# esp32.net
KiCad netlist of a schematic drawn in Altium Designer
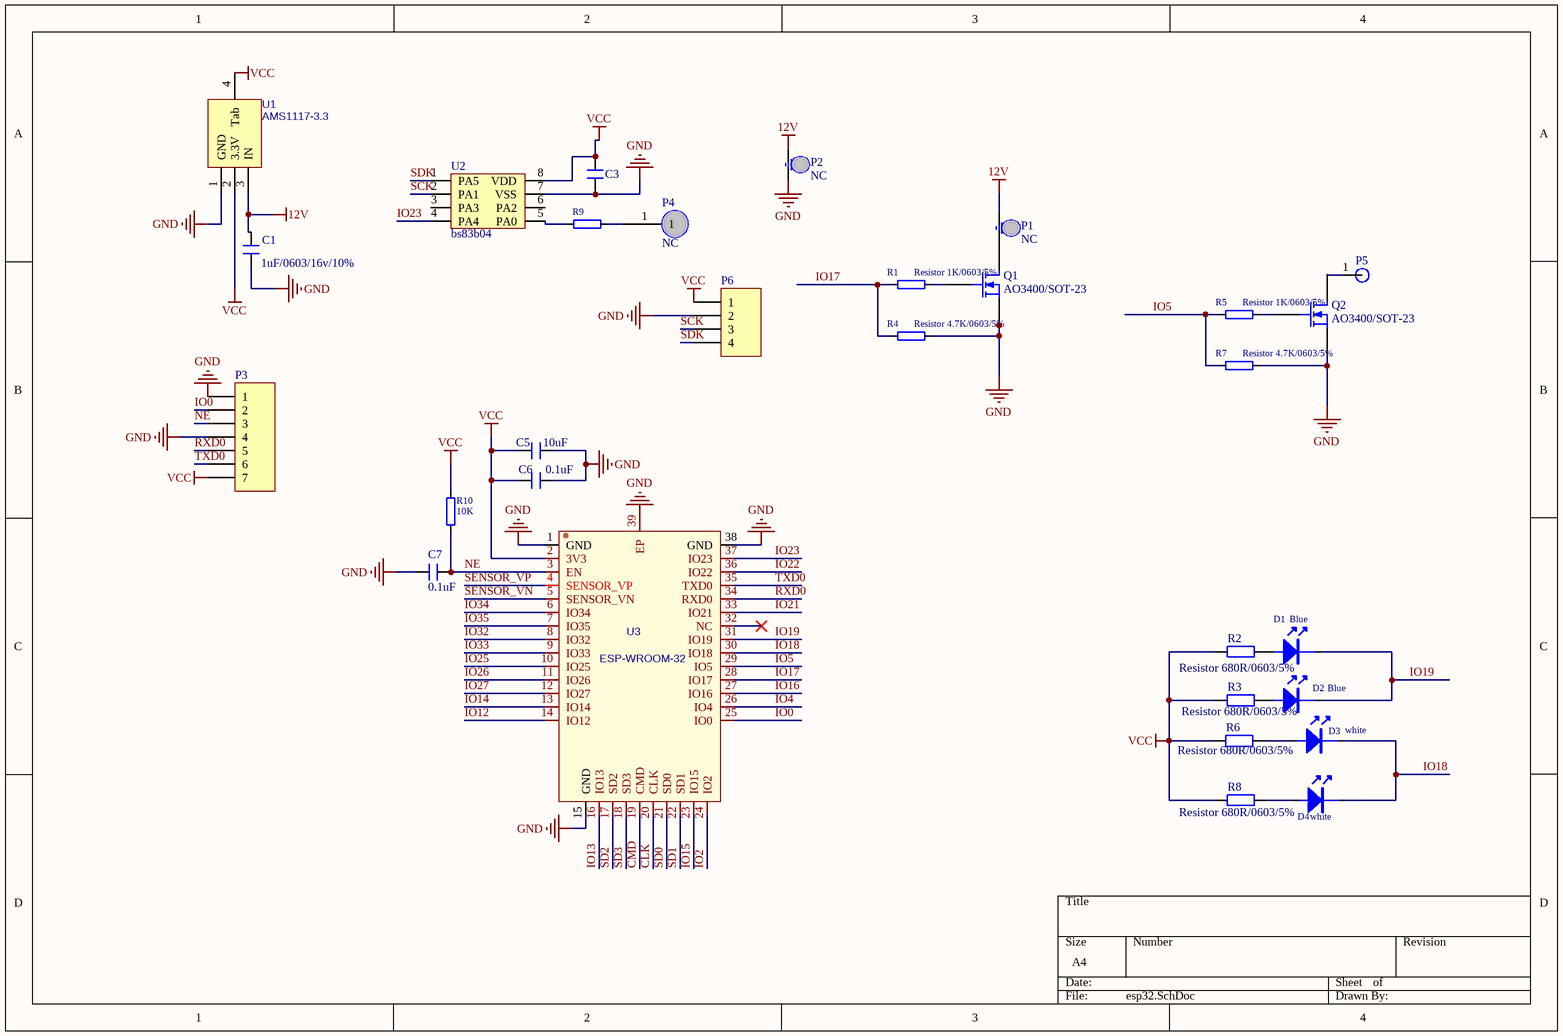
[diagram p0: esp32.SchDoc]

(export (version "E")
  (design (tool "Eeschema 10.0.6"))
  (components
    (comp (ref "C1")
      (value "1uF/0603/16v/10%")
      (footprint "C0603")
      (libsource (lib "Ht_onekey") (part "C0603"))
    )
    (comp (ref "C3")
      (value "100nF")
      (footprint "C0603")
      (description "100nF/0603/16v/10%")
      (libsource (lib "Ht_onekey") (part "C0603"))
    )
    (comp (ref "C5") (value "10uF") (footprint "C0603") (libsource (lib "esp32") (part "C0603")))
    (comp (ref "C6") (value "0.1uF") (footprint "C0603") (libsource (lib "esp32") (part "C0603")))
    (comp (ref "C7") (value "0.1uF") (footprint "C0603") (libsource (lib "esp32") (part "C0603")))
    (comp (ref "D1") (value "Blue") (footprint "1206反贴LED") (libsource (lib "aiwise") (part "LED")))
    (comp (ref "D2") (value "Blue") (footprint "1206反贴LED") (libsource (lib "aiwise") (part "LED")))
    (comp (ref "D3") (value "white") (footprint "1206反贴LED") (libsource (lib "aiwise") (part "LED")))
    (comp (ref "D4") (value "white") (footprint "1206反贴LED") (libsource (lib "aiwise") (part "LED")))
    (comp (ref "P1") (value "NC") (footprint "PAD_2") (libsource (lib "Ht_onekey") (part "Light")))
    (comp (ref "P2") (value "NC") (footprint "PAD_2") (libsource (lib "Ht_onekey") (part "Light")))
    (comp (ref "P3")
      (value "Header 7")
      (footprint "HDR1X7")
      (description "Header, 7-Pin")
      (fields (field (name "PUBLISHER") "Altium Limited"))
      (libsource (lib "Miscellaneous Connectors") (part "Header 7"))
    )
    (comp (ref "P4") (value "NC") (footprint "TOUCH_PAD") (libsource (lib "Ht_onekey") (part "TOUCH_PAD")))
    (comp (ref "P5") (value "PAD") (footprint "PAD") (libsource (lib "esp32") (part "PAD")))
    (comp (ref "P6")
      (value "Header 4")
      (footprint "HDR1X4")
      (description "Header, 4-Pin")
      (fields (field (name "PUBLISHER") "Altium Limited"))
      (libsource (lib "Miscellaneous Connectors") (part "Header 4"))
    )
    (comp (ref "Q1")
      (value "AO3400/SOT-23")
      (footprint "SOT_23_N-MOS")
      (fields (field (name "PUBLISHER") "Altium Limited"))
      (libsource (lib "Miscellaneous Devices") (part "MOSFET-N"))
    )
    (comp (ref "Q2")
      (value "AO3400/SOT-23")
      (footprint "SOT_23_N-MOS")
      (fields (field (name "PUBLISHER") "Altium Limited"))
      (libsource (lib "Miscellaneous Devices") (part "MOSFET-N"))
    )
    (comp (ref "R1") (value "Resistor 1K/0603/5%") (footprint "R0603") (libsource (lib "*") (part "RES")))
    (comp (ref "R2")
      (value "Resistor 680R/0603/5%")
      (footprint "R0603")
      (description "Resistor 2.2K/0603/5%")
      (fields (field (name "PUBLISHER") "Altium Limited"))
      (libsource (lib "Miscellaneous Devices") (part "Res2"))
    )
    (comp (ref "R3")
      (value "Resistor 680R/0603/5%")
      (footprint "R0603")
      (description "Resistor 2.2K/0603/5%")
      (fields (field (name "PUBLISHER") "Altium Limited"))
      (libsource (lib "Miscellaneous Devices") (part "Res2"))
    )
    (comp (ref "R4") (value "Resistor 4.7K/0603/5%") (footprint "R0603") (libsource (lib "*") (part "RES")))
    (comp (ref "R5") (value "Resistor 1K/0603/5%") (footprint "R0603") (libsource (lib "*") (part "RES")))
    (comp (ref "R6")
      (value "Resistor 680R/0603/5%")
      (footprint "R0603")
      (description "Resistor 2.2K/0603/5%")
      (fields (field (name "PUBLISHER") "Altium Limited"))
      (libsource (lib "Miscellaneous Devices") (part "Res2"))
    )
    (comp (ref "R7") (value "Resistor 4.7K/0603/5%") (footprint "R0603") (libsource (lib "*") (part "RES")))
    (comp (ref "R8")
      (value "Resistor 680R/0603/5%")
      (footprint "R0603")
      (description "Resistor 2.2K/0603/5%")
      (fields (field (name "PUBLISHER") "Altium Limited"))
      (libsource (lib "Miscellaneous Devices") (part "Res2"))
    )
    (comp (ref "R9") (value "Resistor 1K/0603/5%") (footprint "R0603") (libsource (lib "*") (part "RES")))
    (comp (ref "R10") (value "10K") (footprint "R0603") (libsource (lib "esp32") (part "RES")))
    (comp (ref "U1")
      (value "AMS1117-3.3")
      (footprint "SOT-223_L6.5-W3.5-P2.30-LS7.0-BR")
      (fields (field (name "BOM_SUPPLIER PART") "C165482") (field (name "CONTRIBUTOR") "LCSC"))
      (libsource (lib "esp32") (part "AMS1117-3.3"))
    )
    (comp (ref "U2")
      (value "bs83b04")
      (footprint "SOP8 - duplicate - duplicate")
      (libsource (lib "esp32") (part "ASC0130C"))
    )
    (comp (ref "U3")
      (value "ESP-WROOM-32")
      (footprint "ESP-WROOM-32")
      (fields (field (name "BOM_SUPPLIER PART") "C95209"))
      (libsource (lib "esp32") (part "ESP-WROOM-32"))
    )
  )
  (nets
    (net (code "1") (name "/CLK") (class "Default")
      (node (ref "U3") (pin "20") (pinfunction "CLK_20") (pintype "passive"))
    )
    (net (code "2") (name "/CMD") (class "Default")
      (node (ref "U3") (pin "19") (pinfunction "CMD_19") (pintype "passive"))
    )
    (net (code "3") (name "/IO0") (class "Default")
      (node (ref "P3") (pin "2") (pinfunction "2_2") (pintype "passive"))
      (node (ref "U3") (pin "25") (pinfunction "IO0_25") (pintype "passive"))
    )
    (net (code "4") (name "/IO2") (class "Default")
      (node (ref "U3") (pin "24") (pinfunction "IO2_24") (pintype "passive"))
    )
    (net (code "5") (name "/IO4") (class "Default")
      (node (ref "U3") (pin "26") (pinfunction "IO4_26") (pintype "passive"))
    )
    (net (code "6") (name "/IO5") (class "Default")
      (node (ref "R5") (pin "2") (pinfunction "2_2") (pintype "passive"))
      (node (ref "R7") (pin "2") (pinfunction "2_2") (pintype "passive"))
      (node (ref "U3") (pin "29") (pinfunction "IO5_29") (pintype "passive"))
    )
    (net (code "7") (name "/IO12") (class "Default")
      (node (ref "U3") (pin "14") (pinfunction "IO12_14") (pintype "passive"))
    )
    (net (code "8") (name "/IO13") (class "Default")
      (node (ref "U3") (pin "16") (pinfunction "IO13_16") (pintype "passive"))
    )
    (net (code "9") (name "/IO14") (class "Default")
      (node (ref "U3") (pin "13") (pinfunction "IO14_13") (pintype "passive"))
    )
    (net (code "10") (name "/IO15") (class "Default")
      (node (ref "U3") (pin "23") (pinfunction "IO15_23") (pintype "passive"))
    )
    (net (code "11") (name "/IO16") (class "Default")
      (node (ref "U3") (pin "27") (pinfunction "IO16_27") (pintype "passive"))
    )
    (net (code "12") (name "/IO17") (class "Default")
      (node (ref "R1") (pin "2") (pinfunction "2_2") (pintype "passive"))
      (node (ref "R4") (pin "2") (pinfunction "2_2") (pintype "passive"))
      (node (ref "U3") (pin "28") (pinfunction "IO17_28") (pintype "passive"))
    )
    (net (code "13") (name "/IO18") (class "Default")
      (node (ref "D3") (pin "K") (pinfunction "2_K") (pintype "passive"))
      (node (ref "D4") (pin "K") (pinfunction "2_K") (pintype "passive"))
      (node (ref "U3") (pin "30") (pinfunction "IO18_30") (pintype "passive"))
    )
    (net (code "14") (name "/IO19") (class "Default")
      (node (ref "D1") (pin "K") (pinfunction "2_K") (pintype "passive"))
      (node (ref "D2") (pin "K") (pinfunction "2_K") (pintype "passive"))
      (node (ref "U3") (pin "31") (pinfunction "IO19_31") (pintype "passive"))
    )
    (net (code "15") (name "/IO21") (class "Default")
      (node (ref "U3") (pin "33") (pinfunction "IO21_33") (pintype "passive"))
    )
    (net (code "16") (name "/IO22") (class "Default")
      (node (ref "U3") (pin "36") (pinfunction "IO22_36") (pintype "passive"))
    )
    (net (code "17") (name "/IO23") (class "Default")
      (node (ref "U2") (pin "4") (pinfunction "PA4_4") (pintype "passive"))
      (node (ref "U3") (pin "37") (pinfunction "IO23_37") (pintype "passive"))
    )
    (net (code "18") (name "/IO25") (class "Default")
      (node (ref "U3") (pin "10") (pinfunction "IO25_10") (pintype "passive"))
    )
    (net (code "19") (name "/IO26") (class "Default")
      (node (ref "U3") (pin "11") (pinfunction "IO26_11") (pintype "passive"))
    )
    (net (code "20") (name "/IO27") (class "Default")
      (node (ref "U3") (pin "12") (pinfunction "IO27_12") (pintype "passive"))
    )
    (net (code "21") (name "/IO32") (class "Default")
      (node (ref "U3") (pin "8") (pinfunction "IO32_8") (pintype "passive"))
    )
    (net (code "22") (name "/IO33") (class "Default")
      (node (ref "U3") (pin "9") (pinfunction "IO33_9") (pintype "passive"))
    )
    (net (code "23") (name "/IO34") (class "Default")
      (node (ref "U3") (pin "6") (pinfunction "IO34_6") (pintype "passive"))
    )
    (net (code "24") (name "/IO35") (class "Default")
      (node (ref "U3") (pin "7") (pinfunction "IO35_7") (pintype "passive"))
    )
    (net (code "25") (name "/NE") (class "Default")
      (node (ref "C7") (pin "2") (pinfunction "2_2") (pintype "passive"))
      (node (ref "P3") (pin "3") (pinfunction "3_3") (pintype "passive"))
      (node (ref "R10") (pin "1") (pinfunction "1_1") (pintype "passive"))
      (node (ref "U3") (pin "3") (pinfunction "EN_3") (pintype "passive"))
    )
    (net (code "26") (name "/RXD0") (class "Default")
      (node (ref "P3") (pin "5") (pinfunction "5_5") (pintype "passive"))
      (node (ref "U3") (pin "34") (pinfunction "RXD0_34") (pintype "passive"))
    )
    (net (code "27") (name "/SCK") (class "Default")
      (node (ref "P6") (pin "3") (pinfunction "3_3") (pintype "passive"))
      (node (ref "U2") (pin "2") (pinfunction "PA1_2") (pintype "passive"))
    )
    (net (code "28") (name "/SD0") (class "Default")
      (node (ref "U3") (pin "21") (pinfunction "SD0_21") (pintype "passive"))
    )
    (net (code "29") (name "/SD1") (class "Default")
      (node (ref "U3") (pin "22") (pinfunction "SD1_22") (pintype "passive"))
    )
    (net (code "30") (name "/SD2") (class "Default")
      (node (ref "U3") (pin "17") (pinfunction "SD2_17") (pintype "passive"))
    )
    (net (code "31") (name "/SD3") (class "Default")
      (node (ref "U3") (pin "18") (pinfunction "SD3_18") (pintype "passive"))
    )
    (net (code "32") (name "/SDK") (class "Default")
      (node (ref "P6") (pin "4") (pinfunction "4_4") (pintype "passive"))
      (node (ref "U2") (pin "1") (pinfunction "PA5_1") (pintype "passive"))
    )
    (net (code "33") (name "/SENSOR_VN") (class "Default")
      (node (ref "U3") (pin "5") (pinfunction "SENSOR_VN_5") (pintype "passive"))
    )
    (net (code "34") (name "/SENSOR_VP") (class "Default")
      (node (ref "U3") (pin "4") (pinfunction "SENSOR_VP_4") (pintype "passive"))
    )
    (net (code "35") (name "/TXD0") (class "Default")
      (node (ref "P3") (pin "6") (pinfunction "6_6") (pintype "passive"))
      (node (ref "U3") (pin "35") (pinfunction "TXD0_35") (pintype "passive"))
    )
    (net (code "36") (name "12V") (class "Default")
      (node (ref "C1") (pin "2") (pinfunction "2_2") (pintype "passive"))
      (node (ref "P1") (pin "1") (pinfunction "1_1") (pintype "passive"))
      (node (ref "P2") (pin "1") (pinfunction "1_1") (pintype "passive"))
      (node (ref "U1") (pin "3") (pinfunction "IN_3") (pintype "passive"))
    )
    (net (code "37") (name "GND") (class "Default")
      (node (ref "C1") (pin "1") (pinfunction "1_1") (pintype "passive"))
      (node (ref "C3") (pin "1") (pinfunction "1_1") (pintype "passive"))
      (node (ref "C5") (pin "1") (pinfunction "1_1") (pintype "passive"))
      (node (ref "C6") (pin "2") (pinfunction "2_2") (pintype "passive"))
      (node (ref "C7") (pin "1") (pinfunction "1_1") (pintype "passive"))
      (node (ref "P2") (pin "2") (pinfunction "2_2") (pintype "passive"))
      (node (ref "P3") (pin "1") (pinfunction "1_1") (pintype "passive"))
      (node (ref "P3") (pin "4") (pinfunction "4_4") (pintype "passive"))
      (node (ref "P6") (pin "2") (pinfunction "2_2") (pintype "passive"))
      (node (ref "Q1") (pin "3") (pinfunction "S_3") (pintype "passive"))
      (node (ref "Q2") (pin "3") (pinfunction "S_3") (pintype "passive"))
      (node (ref "R4") (pin "1") (pinfunction "1_1") (pintype "passive"))
      (node (ref "R7") (pin "1") (pinfunction "1_1") (pintype "passive"))
      (node (ref "U1") (pin "1") (pinfunction "GND_1") (pintype "passive"))
      (node (ref "U2") (pin "7") (pinfunction "VSS_7") (pintype "passive"))
      (node (ref "U3") (pin "1") (pinfunction "GND_1") (pintype "passive"))
      (node (ref "U3") (pin "15") (pinfunction "GND_15") (pintype "passive"))
      (node (ref "U3") (pin "38") (pinfunction "GND_38") (pintype "passive"))
      (node (ref "U3") (pin "39") (pinfunction "EP_39") (pintype "passive"))
    )
    (net (code "38") (name "Net-(D1-1)") (class "Default")
      (node (ref "D1") (pin "A") (pinfunction "1_A") (pintype "passive"))
      (node (ref "R2") (pin "2") (pinfunction "2_2") (pintype "passive"))
    )
    (net (code "39") (name "Net-(D2-1)") (class "Default")
      (node (ref "D2") (pin "A") (pinfunction "1_A") (pintype "passive"))
      (node (ref "R3") (pin "2") (pinfunction "2_2") (pintype "passive"))
    )
    (net (code "40") (name "Net-(D3-1)") (class "Default")
      (node (ref "D3") (pin "A") (pinfunction "1_A") (pintype "passive"))
      (node (ref "R6") (pin "2") (pinfunction "2_2") (pintype "passive"))
    )
    (net (code "41") (name "Net-(D4-1)") (class "Default")
      (node (ref "D4") (pin "A") (pinfunction "1_A") (pintype "passive"))
      (node (ref "R8") (pin "2") (pinfunction "2_2") (pintype "passive"))
    )
    (net (code "42") (name "Net-(P4-Pad1)") (class "Default")
      (node (ref "P4") (pin "1") (pinfunction "1_1") (pintype "passive"))
      (node (ref "R9") (pin "1") (pinfunction "1_1") (pintype "passive"))
    )
    (net (code "43") (name "Net-(Q1-D)") (class "Default")
      (node (ref "P1") (pin "2") (pinfunction "2_2") (pintype "passive"))
      (node (ref "Q1") (pin "1") (pinfunction "D_1") (pintype "passive"))
    )
    (net (code "44") (name "Net-(Q1-G)") (class "Default")
      (node (ref "Q1") (pin "2") (pinfunction "G_2") (pintype "passive"))
      (node (ref "R1") (pin "1") (pinfunction "1_1") (pintype "passive"))
    )
    (net (code "45") (name "Net-(Q2-D)") (class "Default")
      (node (ref "P5") (pin "1") (pinfunction "1_1") (pintype "passive"))
      (node (ref "Q2") (pin "1") (pinfunction "D_1") (pintype "passive"))
    )
    (net (code "46") (name "Net-(Q2-G)") (class "Default")
      (node (ref "Q2") (pin "2") (pinfunction "G_2") (pintype "passive"))
      (node (ref "R5") (pin "1") (pinfunction "1_1") (pintype "passive"))
    )
    (net (code "47") (name "Net-(U2-PA0)") (class "Default")
      (node (ref "R9") (pin "2") (pinfunction "2_2") (pintype "passive"))
      (node (ref "U2") (pin "5") (pinfunction "PA0_5") (pintype "passive"))
    )
    (net (code "48") (name "VCC") (class "Default")
      (node (ref "C3") (pin "2") (pinfunction "2_2") (pintype "passive"))
      (node (ref "C5") (pin "2") (pinfunction "2_2") (pintype "passive"))
      (node (ref "C6") (pin "1") (pinfunction "1_1") (pintype "passive"))
      (node (ref "P3") (pin "7") (pinfunction "7_7") (pintype "passive"))
      (node (ref "P6") (pin "1") (pinfunction "1_1") (pintype "passive"))
      (node (ref "R10") (pin "2") (pinfunction "2_2") (pintype "passive"))
      (node (ref "R2") (pin "1") (pinfunction "1_1") (pintype "passive"))
      (node (ref "R3") (pin "1") (pinfunction "1_1") (pintype "passive"))
      (node (ref "R6") (pin "1") (pinfunction "1_1") (pintype "passive"))
      (node (ref "R8") (pin "1") (pinfunction "1_1") (pintype "passive"))
      (node (ref "U1") (pin "2") (pinfunction "3.3V_2") (pintype "passive"))
      (node (ref "U1") (pin "4") (pinfunction "Tab_4") (pintype "passive"))
      (node (ref "U2") (pin "8") (pinfunction "VDD_8") (pintype "passive"))
      (node (ref "U3") (pin "2") (pinfunction "3V3_2") (pintype "passive"))
    )
    (net (code "49") (name "unconnected-(U2-PA2-Pad6)") (class "Default")
      (node (ref "U2") (pin "6") (pinfunction "PA2_6") (pintype "passive"))
    )
    (net (code "50") (name "unconnected-(U2-PA3-Pad3)") (class "Default")
      (node (ref "U2") (pin "3") (pinfunction "PA3_3") (pintype "passive"))
    )
    (net (code "51") (name "unconnected-(U3-NC-Pad32)") (class "Default")
      (node (ref "U3") (pin "32") (pinfunction "NC_32") (pintype "passive+no_connect"))
    )
  )
)
